# EnviroNode.net
KiCad netlist of a schematic drawn in Altium Designer
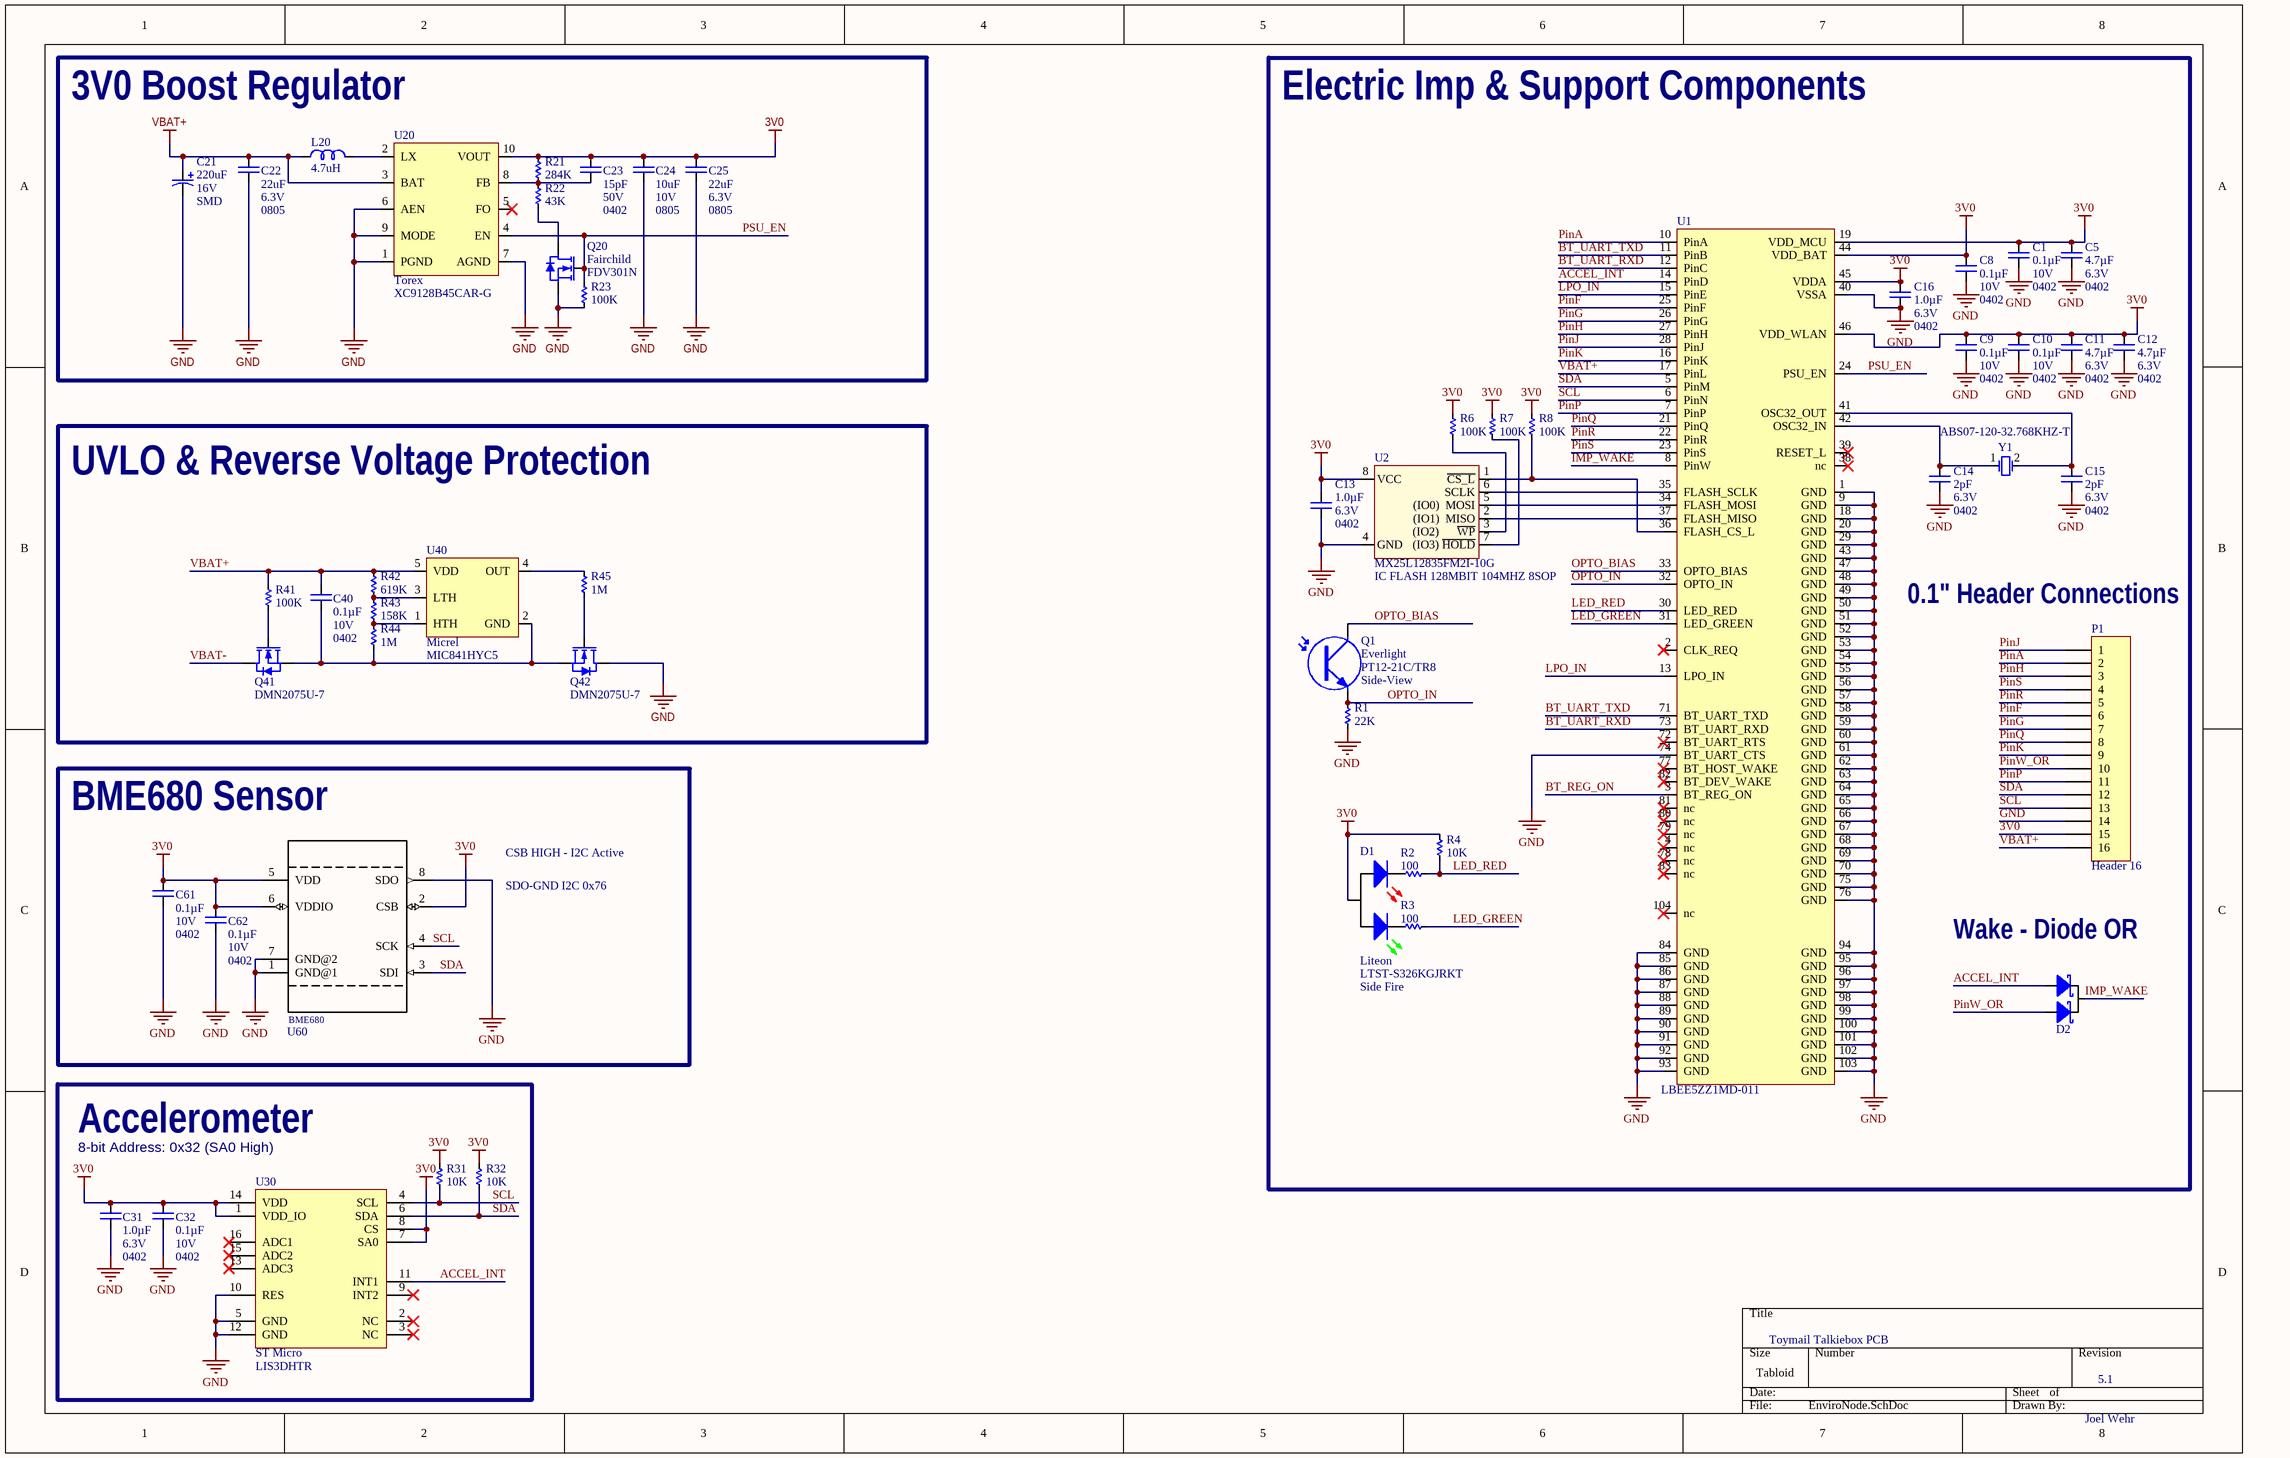
[diagram p0: EnviroNode.SchDoc]

(export (version "E")
  (design (tool "Eeschema 10.0.6"))
  (components
    (comp (ref "C1")
      (value "0.1µF")
      (footprint "Verified Components:CAPC1005X07N")
      (description "CAP CER 0.1UF 10V X5R 0402")
      (fields
        (field (name "TOLERANCE") "10%")
        (field (name "MANUFACTURER") "Taiyo Yuden")
        (field (name "VOLTAGE") "10V")
        (field (name "PACKAGE") "0402")
      )
      (libsource (lib "Verified Components") (part "CAP CER 0.1UF 10V X5R 0402"))
    )
    (comp (ref "C5")
      (value "4.7µF")
      (footprint "Verified Components:CAPC1005X07N")
      (description "CAP CER 4.7UF 6.3V X5R 0402")
      (fields
        (field (name "TOLERANCE") "10%")
        (field (name "MANUFACTURER") "Samsung Electro-Mechanics")
        (field (name "VOLTAGE") "6.3V")
        (field (name "PACKAGE") "0402")
      )
      (libsource (lib "Verified Components") (part "CAP CER 4.7UF 6.3V X5R 0402"))
    )
    (comp (ref "C8")
      (value "0.1µF")
      (footprint "Verified Components:CAPC1005X07N")
      (description "CAP CER 0.1UF 10V X5R 0402")
      (fields
        (field (name "TOLERANCE") "10%")
        (field (name "MANUFACTURER") "Taiyo Yuden")
        (field (name "VOLTAGE") "10V")
        (field (name "PACKAGE") "0402")
      )
      (libsource (lib "Verified Components") (part "CAP CER 0.1UF 10V X5R 0402"))
    )
    (comp (ref "C9")
      (value "0.1µF")
      (footprint "Verified Components:CAPC1005X07N")
      (description "CAP CER 0.1UF 10V X5R 0402")
      (fields
        (field (name "TOLERANCE") "10%")
        (field (name "MANUFACTURER") "Taiyo Yuden")
        (field (name "VOLTAGE") "10V")
        (field (name "PACKAGE") "0402")
      )
      (libsource (lib "Verified Components") (part "CAP CER 0.1UF 10V X5R 0402"))
    )
    (comp (ref "C10")
      (value "0.1µF")
      (footprint "Verified Components:CAPC1005X07N")
      (description "CAP CER 0.1UF 10V X5R 0402")
      (fields
        (field (name "TOLERANCE") "10%")
        (field (name "MANUFACTURER") "Taiyo Yuden")
        (field (name "VOLTAGE") "10V")
        (field (name "PACKAGE") "0402")
      )
      (libsource (lib "Verified Components") (part "CAP CER 0.1UF 10V X5R 0402"))
    )
    (comp (ref "C11")
      (value "4.7µF")
      (footprint "Verified Components:CAPC1005X07N")
      (description "CAP CER 4.7UF 6.3V X5R 0402")
      (fields
        (field (name "TOLERANCE") "10%")
        (field (name "MANUFACTURER") "Samsung Electro-Mechanics")
        (field (name "VOLTAGE") "6.3V")
        (field (name "PACKAGE") "0402")
      )
      (libsource (lib "Verified Components") (part "CAP CER 4.7UF 6.3V X5R 0402"))
    )
    (comp (ref "C12")
      (value "4.7µF")
      (footprint "Verified Components:CAPC1005X07N")
      (description "CAP CER 4.7UF 6.3V X5R 0402")
      (fields
        (field (name "TOLERANCE") "10%")
        (field (name "MANUFACTURER") "Samsung Electro-Mechanics")
        (field (name "VOLTAGE") "6.3V")
        (field (name "PACKAGE") "0402")
      )
      (libsource (lib "Verified Components") (part "CAP CER 4.7UF 6.3V X5R 0402"))
    )
    (comp (ref "C13")
      (value "1.0µF")
      (footprint "Verified Components:CAPC1005X07N")
      (description "CAP CER 1.0UF 6.3V X7R 0402")
      (fields
        (field (name "TOLERANCE") "10%")
        (field (name "VOLTAGE") "6.3V")
        (field (name "PACKAGE") "0402")
      )
      (libsource (lib "Verified Components") (part "CAP CER 1.0UF 6.3V X7R 0402"))
    )
    (comp (ref "C14")
      (value "2pF")
      (footprint "Verified Components:CAPC1005X07N")
      (description "CAP CER 2pF 6.3V X7R 0402")
      (fields
        (field (name "TOLERANCE") "10%")
        (field (name "VOLTAGE") "6.3V")
        (field (name "PACKAGE") "0402")
      )
      (libsource (lib "Verified Components") (part "CAP CER 2pF 6.3V X7R 0402"))
    )
    (comp (ref "C15")
      (value "2pF")
      (footprint "Verified Components:CAPC1005X07N")
      (description "CAP CER 2pF 6.3V X7R 0402")
      (fields
        (field (name "TOLERANCE") "10%")
        (field (name "VOLTAGE") "6.3V")
        (field (name "PACKAGE") "0402")
      )
      (libsource (lib "Verified Components") (part "CAP CER 2pF 6.3V X7R 0402"))
    )
    (comp (ref "C16")
      (value "1.0µF")
      (footprint "Verified Components:CAPC1005X07N")
      (description "CAP CER 1.0UF 6.3V X7R 0402")
      (fields
        (field (name "TOLERANCE") "10%")
        (field (name "VOLTAGE") "6.3V")
        (field (name "PACKAGE") "0402")
      )
      (libsource (lib "Verified Components") (part "CAP CER 1.0UF 6.3V X7R 0402"))
    )
    (comp (ref "C21")
      (value "220uF")
      (footprint "Verified Components:UWT1C221MCL1GS")
      (description "CAP,ALUM POLYMER,220uF,20%,16V,SMD")
      (fields
        (field (name "TOLERANCE") "20%")
        (field (name "PART NUMBER") "CAPP00124")
        (field (name "VOLTAGE") "16V")
        (field (name "PACKAGE") "SMD")
      )
      (libsource (lib "Verified Components") (part "CAP,ALUM POLYMER,220uF,20%,16V,SMD"))
    )
    (comp (ref "C22")
      (value "22uF")
      (footprint "Verified Components:CAPC2012X14N")
      (description "CAP CER 22UF 6.3V X5R 0805")
      (fields
        (field (name "TOLERANCE") "20%")
        (field (name "PART NUMBER") "CAPC00039")
        (field (name "VOLTAGE") "6.3V")
        (field (name "PACKAGE") "0805")
      )
      (libsource (lib "Verified Components") (part "CAP CER 22UF 6.3V X5R 0805"))
    )
    (comp (ref "C23")
      (value "15pF")
      (footprint "Verified Components:CAPC1005X07N")
      (description "CAP CER 15PF 50V C0G/NP0 0402")
      (fields
        (field (name "TOLERANCE") "5%")
        (field (name "MANUFACTURER") "Murata Electronics North America")
        (field (name "VOLTAGE") "50V")
        (field (name "PACKAGE") "0402")
      )
      (libsource (lib "Verified Components") (part "CAP CER 13PF 50V C0G/NP0 0402"))
    )
    (comp (ref "C24")
      (value "10uF")
      (footprint "Verified Components:CAPC2012X14N")
      (description "CAP CER 10UF 10V X5R 0805")
      (fields
        (field (name "TOLERANCE") "20%")
        (field (name "PART NUMBER") "CAPC00039")
        (field (name "VOLTAGE") "10V")
        (field (name "PACKAGE") "0805")
      )
      (libsource (lib "Verified Components") (part "CAP CER 10UF 10V X5R 0805"))
    )
    (comp (ref "C25")
      (value "22uF")
      (footprint "Verified Components:CAPC2012X14N")
      (description "CAP CER 22UF 6.3V X5R 0805")
      (fields
        (field (name "TOLERANCE") "20%")
        (field (name "PART NUMBER") "CAPC00039")
        (field (name "VOLTAGE") "6.3V")
        (field (name "PACKAGE") "0805")
      )
      (libsource (lib "Verified Components") (part "CAP CER 22UF 6.3V X5R 0805"))
    )
    (comp (ref "C31")
      (value "1.0µF")
      (footprint "Verified Components:CAPC1005X07N")
      (description "CAP CER 1.0UF 6.3V X7R 0402")
      (fields
        (field (name "TOLERANCE") "10%")
        (field (name "VOLTAGE") "6.3V")
        (field (name "PACKAGE") "0402")
      )
      (libsource (lib "Verified Components") (part "CAP CER 1.0UF 6.3V X7R 0402"))
    )
    (comp (ref "C32")
      (value "0.1µF")
      (footprint "Verified Components:CAPC1005X07N")
      (description "CAP CER 0.1UF 10V X5R 0402")
      (fields
        (field (name "TOLERANCE") "10%")
        (field (name "MANUFACTURER") "Taiyo Yuden")
        (field (name "VOLTAGE") "10V")
        (field (name "PACKAGE") "0402")
      )
      (libsource (lib "Verified Components") (part "CAP CER 0.1UF 10V X5R 0402"))
    )
    (comp (ref "C40")
      (value "0.1µF")
      (footprint "Verified Components:CAPC1005X07N")
      (description "CAP CER 0.1UF 10V X5R 0402")
      (fields
        (field (name "TOLERANCE") "10%")
        (field (name "MANUFACTURER") "Taiyo Yuden")
        (field (name "VOLTAGE") "10V")
        (field (name "PACKAGE") "0402")
      )
      (libsource (lib "Verified Components") (part "CAP CER 0.1UF 10V X5R 0402"))
    )
    (comp (ref "C61")
      (value "0.1µF")
      (footprint "Verified Components:CAPC1005X07N")
      (description "CAP CER 0.1UF 10V X5R 0402")
      (fields
        (field (name "TOLERANCE") "10%")
        (field (name "MANUFACTURER") "Taiyo Yuden")
        (field (name "VOLTAGE") "10V")
        (field (name "PACKAGE") "0402")
      )
      (libsource (lib "Verified Components") (part "CAP CER 0.1UF 10V X5R 0402"))
    )
    (comp (ref "C62")
      (value "0.1µF")
      (footprint "Verified Components:CAPC1005X07N")
      (description "CAP CER 0.1UF 10V X5R 0402")
      (fields
        (field (name "TOLERANCE") "10%")
        (field (name "MANUFACTURER") "Taiyo Yuden")
        (field (name "VOLTAGE") "10V")
        (field (name "PACKAGE") "0402")
      )
      (libsource (lib "Verified Components") (part "CAP CER 0.1UF 10V X5R 0402"))
    )
    (comp (ref "D1")
      (value "LED Red and Green")
      (footprint "Verified Components:LTST-S326KGJRKT")
      (description "LED, Dual, Side-view, Red-Green,2V, Common Anode, SMT")
      (fields
        (field (name "PART NUMBER") "LED00016")
        (field (name "MANUFACTURER") "Liteon")
        (field (name "MANUFACTURER PART NUMBER") "LTST-S326KGJRKT")
        (field (name "ORIENTATION") "Side Fire")
      )
      (libsource (lib "Verified Components") (part "LED_REDGREEN_CA"))
    )
    (comp (ref "D2")
      (value "Dual Schottky Diode")
      (footprint "Verified Components:SOT95P300X130-3N")
      (description "DIODE, Schottky, 200mA, 30V, Dual, Common Cathode, SOT23")
      (fields (field (name "PART NUMBER") "SCHOTTKY00009") (field (name "MANUFACTURER") "Fairchild"))
      (libsource (lib "Verified Components") (part "BAT54C"))
    )
    (comp (ref "L20")
      (value "4.7uH")
      (footprint "Verified Components:INDP6060X28N")
      (description "FIXED IND 4.7UH 3A 40.3 MOHM SMD")
      (fields (field (name "PART NUMBER") "IND00007") (field (name "MANUFACTURER") "Taiyo Yuden"))
      (libsource (lib "Verified Components") (part "NR6028T4R7M"))
    )
    (comp (ref "P1")
      (value "Header 16")
      (footprint "HDR1X16")
      (description "Header, 16-Pin")
      (fields (field (name "PUBLISHER") "Altium Limited"))
      (libsource (lib "Miscellaneous Connectors") (part "Header 16"))
    )
    (comp (ref "Q1")
      (value "PHOTOTRANSISTOR")
      (footprint "Verified Components:PT12-21C")
      (description "Phototrans, Clear, Side-view, 940nm, 0.4V, 1.14mA, SMT")
      (fields
        (field (name "PART NUMBER") "PHOTO00004")
        (field (name "MANUFACTURER") "Everlight")
        (field (name "MANUFACTURER PART NUMBER") "PT12-21C/TR8")
        (field (name "ORIENTATION") "Side-View")
      )
      (libsource (lib "Verified Components") (part "PHOTOTRANSISTOR"))
    )
    (comp (ref "Q20")
      (value "N-Channel MOSFET")
      (footprint "SOT95P300X130-3N")
      (description "NFET")
      (fields
        (field (name "PART NUMBER") "NFET00004")
        (field (name "MANUFACTURER") "Fairchild")
        (field (name "MANUFACTURER PART NUMBER") "FDV301N")
      )
      (libsource (lib "Verified Components") (part "DMN2075U-7"))
    )
    (comp (ref "Q41")
      (value "N-Channel MOSFET")
      (footprint "Verified Components:SOT95P300X130-3N")
      (description "NFET, 20V, 4.2A, SOT23")
      (fields
        (field (name "PART NUMBER") "NFET00004")
        (field (name "MANUFACTURER") "Diodes Incorporated")
        (field (name "MANUFACTURER PART NUMBER") "DMN2075U-7")
      )
      (libsource (lib "Verified Components") (part "DMN2075U-7"))
    )
    (comp (ref "Q42")
      (value "N-Channel MOSFET")
      (footprint "SOT95P300X130-3N")
      (description "NFET, 20V, 4.2A, SOT23")
      (fields
        (field (name "PART NUMBER") "NFET00004")
        (field (name "MANUFACTURER") "Diodes Incorporated")
        (field (name "MANUFACTURER PART NUMBER") "DMN2075U-7")
      )
      (libsource (lib "Verified Components") (part "DMN2075U-7"))
    )
    (comp (ref "R1")
      (value "22K")
      (footprint "Verified Components:RESC1005X04N")
      (description "RES SMD 22K OHM 1% 1/16W 0402")
      (fields (field (name "POWER") "0.063W") (field (name "MANUFACTURER") "Samsung"))
      (libsource (lib "Verified Components") (part "RES SMD 22K OHM 1% 1/16W 0402"))
    )
    (comp (ref "R2")
      (value "100")
      (footprint "Verified Components:RESC1005X04N")
      (description "RES SMD 100 OHM 5% 1/16W 0402")
      (fields (field (name "POWER") "0.063W") (field (name "TOLERANCE") "5%"))
      (libsource (lib "Verified Components") (part "RES SMD 100 OHM 5% 1/16W 0402"))
    )
    (comp (ref "R3")
      (value "100")
      (footprint "Verified Components:RESC1005X04N")
      (description "RES SMD 100 OHM 5% 1/16W 0402")
      (fields (field (name "POWER") "0.063W") (field (name "TOLERANCE") "5%"))
      (libsource (lib "Verified Components") (part "RES SMD 100 OHM 5% 1/16W 0402"))
    )
    (comp (ref "R4")
      (value "10K")
      (footprint "Verified Components:RESC1005X04N")
      (description "RES SMD 10K OHM 1% 1/16W 0402")
      (fields (field (name "POWER") "0.063W") (field (name "TOLERANCE") "1%"))
      (libsource (lib "Verified Components") (part "RES SMD 10K OHM 1% 1/16W 0402"))
    )
    (comp (ref "R6")
      (value "100K")
      (footprint "Verified Components:RESC1005X04N")
      (description "RES SMD 100K OHM 5% 1/16W 0402")
      (fields (field (name "PART NUMBER") "RES00001") (field (name "POWER") "0.063W"))
      (libsource (lib "Verified Components") (part "RES SMD 100K OHM 5% 1/16W 0402"))
    )
    (comp (ref "R7")
      (value "100K")
      (footprint "Verified Components:RESC1005X04N")
      (description "RES SMD 100K OHM 5% 1/16W 0402")
      (fields (field (name "PART NUMBER") "RES00001") (field (name "POWER") "0.063W"))
      (libsource (lib "Verified Components") (part "RES SMD 100K OHM 5% 1/16W 0402"))
    )
    (comp (ref "R8")
      (value "100K")
      (footprint "Verified Components:RESC1005X04N")
      (description "RES SMD 100K OHM 5% 1/16W 0402")
      (fields (field (name "PART NUMBER") "RES00001") (field (name "POWER") "0.063W"))
      (libsource (lib "Verified Components") (part "RES SMD 100K OHM 5% 1/16W 0402"))
    )
    (comp (ref "R21")
      (value "284K")
      (footprint "Verified Components:RESC1005X04N")
      (description "RES SMD 220K OHM 1% 1/16W 0402")
      (fields (field (name "POWER") "0.063W") (field (name "MANUFACTURER") "Samsung"))
      (libsource (lib "Verified Components") (part "RES SMD 22K OHM 1% 1/16W 0402"))
    )
    (comp (ref "R22")
      (value "43K")
      (footprint "Verified Components:RESC1005X04N")
      (description "RES SMD 43K OHM 1% 1/16W 0402")
      (fields (field (name "POWER") "0.063W") (field (name "MANUFACTURER") "Samsung"))
      (libsource (lib "Verified Components") (part "RES SMD 22K OHM 1% 1/16W 0402"))
    )
    (comp (ref "R23")
      (value "100K")
      (footprint "Verified Components:RESC1005X04N")
      (description "RES SMD 100K OHM 5% 1/16W 0402")
      (fields (field (name "PART NUMBER") "RES00001") (field (name "POWER") "0.063W"))
      (libsource (lib "Verified Components") (part "RES SMD 100K OHM 5% 1/16W 0402"))
    )
    (comp (ref "R31")
      (value "10K")
      (footprint "Verified Components:RESC1005X04N")
      (description "RES SMD 10K OHM 1% 1/16W 0402")
      (fields (field (name "POWER") "0.063W") (field (name "TOLERANCE") "1%"))
      (libsource (lib "Verified Components") (part "RES SMD 10K OHM 1% 1/16W 0402"))
    )
    (comp (ref "R32")
      (value "10K")
      (footprint "Verified Components:RESC1005X04N")
      (description "RES SMD 10K OHM 1% 1/16W 0402")
      (fields (field (name "POWER") "0.063W") (field (name "TOLERANCE") "1%"))
      (libsource (lib "Verified Components") (part "RES SMD 10K OHM 1% 1/16W 0402"))
    )
    (comp (ref "R41")
      (value "100K")
      (footprint "Verified Components:RESC1005X04N")
      (description "RES SMD 100K OHM 5% 1/16W 0402")
      (fields (field (name "PART NUMBER") "RES00001") (field (name "POWER") "0.063W"))
      (libsource (lib "Verified Components") (part "RES SMD 100K OHM 5% 1/16W 0402"))
    )
    (comp (ref "R42")
      (value "619K")
      (footprint "Verified Components:RESC1005X04N")
      (description "RES SMD 1M OHM 1% 1/16W 0402")
      (fields (field (name "POWER") "0.063W") (field (name "MANUFACTURER") "Samsung"))
      (libsource (lib "Verified Components") (part "RES SMD 1M OHM 1% 1/16W 0402"))
    )
    (comp (ref "R43")
      (value "158K")
      (footprint "Verified Components:RESC1005X04N")
      (description "RES SMD 1M OHM 1% 1/16W 0402")
      (fields (field (name "POWER") "0.063W") (field (name "MANUFACTURER") "Samsung"))
      (libsource (lib "Verified Components") (part "RES SMD 1M OHM 1% 1/16W 0402"))
    )
    (comp (ref "R44")
      (value "1M")
      (footprint "Verified Components:RESC1005X04N")
      (description "RES SMD 1M OHM 1% 1/16W 0402")
      (fields (field (name "POWER") "0.063W") (field (name "MANUFACTURER") "Samsung"))
      (libsource (lib "Verified Components") (part "RES SMD 1M OHM 1% 1/16W 0402"))
    )
    (comp (ref "R45")
      (value "1M")
      (footprint "Verified Components:RESC1005X04N")
      (description "RES SMD 1M OHM 1% 1/16W 0402")
      (fields (field (name "POWER") "0.063W") (field (name "MANUFACTURER") "Samsung"))
      (libsource (lib "Verified Components") (part "RES SMD 1M OHM 1% 1/16W 0402"))
    )
    (comp (ref "U1")
      (value "Murata Imp004m Module")
      (footprint "Verified Components:LBEE5ZZ1MD")
      (fields
        (field (name "MANUFACTURER") "Murata Electronics North America")
        (field (name "MANUFACTURER PART NUMBER") "LBEE5ZZ1MD-011")
      )
      (libsource (lib "Integrated_Library") (part "LBEE5ZZ1MD"))
    )
    (comp (ref "U2")
      (value "IC FLASH 128MBIT 104MHZ 8SOP")
      (footprint "Verified Components:SOP127P790X216-8N")
      (fields
        (field (name "MANUFACTURER") "Macronix")
        (field (name "MANUFACTURER PART NUMBER") "MX25L12835FM2I-10G")
      )
      (libsource (lib "Verified Components") (part "IC FLASH 128MBIT 104MHZ 8SOP"))
    )
    (comp (ref "U20")
      (value "XC9128")
      (footprint "MSOP50P490X116-10N")
      (description "IC, DC/DC boost,Adjustable, 6 VIN, 500mA, MSOP10")
      (fields
        (field (name "PART NUMBER") "IC00026")
        (field (name "MANUFACTURER") "Torex")
        (field (name "MANUFACTURER PART NUMBER") "XC9128B45CAR-G")
      )
      (libsource (lib "Verified Components") (part "XC9128"))
    )
    (comp (ref "U30")
      (value "LIS3DHTR")
      (footprint "Verified Components:LGA50P300X300X100-16N-ST")
      (description "IC, Accelerometer, 3-Axis, Low Power, 16-bit, LGA16")
      (fields
        (field (name "PART NUMBER") "IC00038")
        (field (name "MANUFACTURER") "ST Micro")
        (field (name "MANUFACTURER PART NUMBER") "LIS3DHTR")
      )
      (libsource (lib "Verified Components") (part "LIS3DHTR"))
    )
    (comp (ref "U40")
      (value "MIC841")
      (footprint "Verified Components:SOT65P200X125-5N")
      (description "IC, Comparator with Reference and Programmable Hysteresis, SOT-353")
      (fields
        (field (name "PART NUMBER") "IC00032")
        (field (name "MANUFACTURER") "Micrel")
        (field (name "MANUFACTURER PART NUMBER") "MIC841HYC5")
      )
      (libsource (lib "Verified Components") (part "MIC841"))
    )
    (comp (ref "U60")
      (value "BME680")
      (footprint "Verified Components:BME680")
      (description "Integrated Environmental Unit")
      (fields (field (name "MF") "Bosch"))
      (libsource (lib "Verified Components") (part "BME680"))
    )
    (comp (ref "Y1")
      (value "XTAL_COMPACT")
      (footprint "Verified Components:XTAL_32X15X09-2N")
      (description "XTAL, 32.768kHz, 20ppm, 6pF, 60K Ohm, 3215")
      (fields
        (field (name "MANUFACTURER") "Abracon")
        (field (name "PART NUMBER") "XTAL00004")
        (field (name "MANUFACTURER PART NUMBER") "ABS07-120-32.768KHZ-T")
      )
      (libsource (lib "Verified Components") (part "XTAL_COMPACT"))
    )
  )
  (nets
    (net (code "1") (name "/ACCEL_INT") (class "Default")
      (node (ref "D2") (pin "1") (pinfunction "1_1") (pintype "passive"))
      (node (ref "U1") (pin "14") (pinfunction "PinD_14") (pintype "passive"))
      (node (ref "U30") (pin "11") (pinfunction "INT1_11") (pintype "passive"))
    )
    (net (code "2") (name "/BT_REG_ON") (class "Default")
      (node (ref "U1") (pin "3") (pinfunction "BT_REG_ON_3") (pintype "passive"))
    )
    (net (code "3") (name "/BT_UART_RXD") (class "Default")
      (node (ref "U1") (pin "12") (pinfunction "PinC_12") (pintype "passive"))
      (node (ref "U1") (pin "73") (pinfunction "BT_UART_RXD_73") (pintype "passive"))
    )
    (net (code "4") (name "/BT_UART_TXD") (class "Default")
      (node (ref "U1") (pin "11") (pinfunction "PinB_11") (pintype "passive"))
      (node (ref "U1") (pin "71") (pinfunction "BT_UART_TXD_71") (pintype "passive"))
    )
    (net (code "5") (name "/IMP_WAKE") (class "Default")
      (node (ref "D2") (pin "3") (pinfunction "3_3") (pintype "passive"))
      (node (ref "U1") (pin "8") (pinfunction "PinW_8") (pintype "passive"))
    )
    (net (code "6") (name "/LED_GREEN") (class "Default")
      (node (ref "R3") (pin "2") (pinfunction "2_2") (pintype "passive"))
      (node (ref "U1") (pin "31") (pinfunction "LED_GREEN_31") (pintype "passive"))
    )
    (net (code "7") (name "/LED_RED") (class "Default")
      (node (ref "R2") (pin "2") (pinfunction "2_2") (pintype "passive"))
      (node (ref "R4") (pin "2") (pinfunction "2_2") (pintype "passive"))
      (node (ref "U1") (pin "30") (pinfunction "LED_RED_30") (pintype "passive"))
    )
    (net (code "8") (name "/LPO_IN") (class "Default")
      (node (ref "U1") (pin "13") (pinfunction "LPO_IN_13") (pintype "passive"))
      (node (ref "U1") (pin "15") (pinfunction "PinE_15") (pintype "passive"))
    )
    (net (code "9") (name "/OPTO_BIAS") (class "Default")
      (node (ref "Q1") (pin "C") (pinfunction "C_C") (pintype "passive"))
      (node (ref "U1") (pin "33") (pinfunction "OPTO_BIAS_33") (pintype "passive"))
    )
    (net (code "10") (name "/OPTO_IN") (class "Default")
      (node (ref "Q1") (pin "E") (pinfunction "E_E") (pintype "passive"))
      (node (ref "R1") (pin "1") (pinfunction "1_1") (pintype "passive"))
      (node (ref "U1") (pin "32") (pinfunction "OPTO_IN_32") (pintype "passive"))
    )
    (net (code "11") (name "/PSU_EN") (class "Default")
      (node (ref "Q20") (pin "1") (pinfunction "G_1") (pintype "passive"))
      (node (ref "R23") (pin "1") (pinfunction "1_1") (pintype "passive"))
      (node (ref "U1") (pin "24") (pinfunction "PSU_EN_24") (pintype "passive"))
      (node (ref "U20") (pin "4") (pinfunction "EN_4") (pintype "passive"))
    )
    (net (code "12") (name "/PinA") (class "Default")
      (node (ref "P1") (pin "2") (pinfunction "2_2") (pintype "passive"))
      (node (ref "U1") (pin "10") (pinfunction "PinA_10") (pintype "passive"))
    )
    (net (code "13") (name "/PinF") (class "Default")
      (node (ref "P1") (pin "6") (pinfunction "6_6") (pintype "passive"))
      (node (ref "U1") (pin "25") (pinfunction "PinF_25") (pintype "passive"))
    )
    (net (code "14") (name "/PinG") (class "Default")
      (node (ref "P1") (pin "7") (pinfunction "7_7") (pintype "passive"))
      (node (ref "U1") (pin "26") (pinfunction "PinG_26") (pintype "passive"))
    )
    (net (code "15") (name "/PinH") (class "Default")
      (node (ref "P1") (pin "3") (pinfunction "3_3") (pintype "passive"))
      (node (ref "U1") (pin "27") (pinfunction "PinH_27") (pintype "passive"))
    )
    (net (code "16") (name "/PinJ") (class "Default")
      (node (ref "P1") (pin "1") (pinfunction "1_1") (pintype "passive"))
      (node (ref "U1") (pin "28") (pinfunction "PinJ_28") (pintype "passive"))
    )
    (net (code "17") (name "/PinK") (class "Default")
      (node (ref "P1") (pin "9") (pinfunction "9_9") (pintype "passive"))
      (node (ref "U1") (pin "16") (pinfunction "PinK_16") (pintype "passive"))
    )
    (net (code "18") (name "/PinP") (class "Default")
      (node (ref "P1") (pin "11") (pinfunction "11_11") (pintype "passive"))
      (node (ref "U1") (pin "7") (pinfunction "PinP_7") (pintype "passive"))
    )
    (net (code "19") (name "/PinQ") (class "Default")
      (node (ref "P1") (pin "8") (pinfunction "8_8") (pintype "passive"))
      (node (ref "U1") (pin "21") (pinfunction "PinQ_21") (pintype "passive"))
    )
    (net (code "20") (name "/PinR") (class "Default")
      (node (ref "P1") (pin "5") (pinfunction "5_5") (pintype "passive"))
      (node (ref "U1") (pin "22") (pinfunction "PinR_22") (pintype "passive"))
    )
    (net (code "21") (name "/PinS") (class "Default")
      (node (ref "P1") (pin "4") (pinfunction "4_4") (pintype "passive"))
      (node (ref "U1") (pin "23") (pinfunction "PinS_23") (pintype "passive"))
    )
    (net (code "22") (name "/PinW_OR") (class "Default")
      (node (ref "D2") (pin "2") (pinfunction "2_2") (pintype "open_emitter"))
      (node (ref "P1") (pin "10") (pinfunction "10_10") (pintype "passive"))
    )
    (net (code "23") (name "/SCL") (class "Default")
      (node (ref "P1") (pin "13") (pinfunction "13_13") (pintype "passive"))
      (node (ref "R31") (pin "2") (pinfunction "2_2") (pintype "passive"))
      (node (ref "U1") (pin "6") (pinfunction "PinN_6") (pintype "passive"))
      (node (ref "U30") (pin "4") (pinfunction "SCL_4") (pintype "passive"))
      (node (ref "U60") (pin "4") (pinfunction "SCK_4") (pintype "input"))
    )
    (net (code "24") (name "/SDA") (class "Default")
      (node (ref "P1") (pin "12") (pinfunction "12_12") (pintype "passive"))
      (node (ref "R32") (pin "2") (pinfunction "2_2") (pintype "passive"))
      (node (ref "U1") (pin "5") (pinfunction "PinM_5") (pintype "passive"))
      (node (ref "U30") (pin "6") (pinfunction "SDA_6") (pintype "passive"))
      (node (ref "U60") (pin "3") (pinfunction "SDI_3") (pintype "input"))
    )
    (net (code "25") (name "/VBAT-") (class "Default")
      (node (ref "Q41") (pin "3") (pinfunction "D_3") (pintype "passive"))
    )
    (net (code "26") (name "3V0") (class "Default")
      (node (ref "C1") (pin "2") (pinfunction "2_2") (pintype "passive"))
      (node (ref "C10") (pin "2") (pinfunction "2_2") (pintype "passive"))
      (node (ref "C11") (pin "2") (pinfunction "2_2") (pintype "passive"))
      (node (ref "C12") (pin "2") (pinfunction "2_2") (pintype "passive"))
      (node (ref "C13") (pin "2") (pinfunction "2_2") (pintype "passive"))
      (node (ref "C16") (pin "2") (pinfunction "2_2") (pintype "passive"))
      (node (ref "C23") (pin "2") (pinfunction "2_2") (pintype "passive"))
      (node (ref "C24") (pin "2") (pinfunction "2_2") (pintype "passive"))
      (node (ref "C25") (pin "2") (pinfunction "2_2") (pintype "passive"))
      (node (ref "C31") (pin "2") (pinfunction "2_2") (pintype "passive"))
      (node (ref "C32") (pin "2") (pinfunction "2_2") (pintype "passive"))
      (node (ref "C5") (pin "2") (pinfunction "2_2") (pintype "passive"))
      (node (ref "C61") (pin "2") (pinfunction "2_2") (pintype "passive"))
      (node (ref "C62") (pin "2") (pinfunction "2_2") (pintype "passive"))
      (node (ref "C8") (pin "2") (pinfunction "2_2") (pintype "passive"))
      (node (ref "C9") (pin "2") (pinfunction "2_2") (pintype "passive"))
      (node (ref "D1") (pin "A") (pinfunction "A_A") (pintype "passive"))
      (node (ref "P1") (pin "15") (pinfunction "15_15") (pintype "passive"))
      (node (ref "R21") (pin "1") (pinfunction "1_1") (pintype "passive"))
      (node (ref "R31") (pin "1") (pinfunction "1_1") (pintype "passive"))
      (node (ref "R32") (pin "1") (pinfunction "1_1") (pintype "passive"))
      (node (ref "R4") (pin "1") (pinfunction "1_1") (pintype "passive"))
      (node (ref "R6") (pin "1") (pinfunction "1_1") (pintype "passive"))
      (node (ref "R7") (pin "1") (pinfunction "1_1") (pintype "passive"))
      (node (ref "R8") (pin "1") (pinfunction "1_1") (pintype "passive"))
      (node (ref "U1") (pin "19") (pinfunction "VDD_MCU_19") (pintype "passive"))
      (node (ref "U1") (pin "44") (pinfunction "VDD_BAT_44") (pintype "passive"))
      (node (ref "U1") (pin "45") (pinfunction "VDDA_45") (pintype "passive"))
      (node (ref "U1") (pin "46") (pinfunction "VDD_WLAN_46") (pintype "passive"))
      (node (ref "U2") (pin "8") (pinfunction "VCC_8") (pintype "power_in"))
      (node (ref "U20") (pin "10") (pinfunction "VOUT_10") (pintype "passive"))
      (node (ref "U30") (pin "1") (pinfunction "VDD_IO_1") (pintype "power_in"))
      (node (ref "U30") (pin "14") (pinfunction "VDD_14") (pintype "power_in"))
      (node (ref "U30") (pin "7") (pinfunction "SA0_7") (pintype "passive"))
      (node (ref "U30") (pin "8") (pinfunction "CS_8") (pintype "passive"))
      (node (ref "U60") (pin "2") (pinfunction "CSB_2") (pintype "bidirectional"))
      (node (ref "U60") (pin "5") (pinfunction "VDD_5") (pintype "power_in"))
      (node (ref "U60") (pin "6") (pinfunction "VDDIO_6") (pintype "bidirectional"))
    )
    (net (code "27") (name "GND") (class "Default")
      (node (ref "C1") (pin "1") (pinfunction "1_1") (pintype "passive"))
      (node (ref "C10") (pin "1") (pinfunction "1_1") (pintype "passive"))
      (node (ref "C11") (pin "1") (pinfunction "1_1") (pintype "passive"))
      (node (ref "C12") (pin "1") (pinfunction "1_1") (pintype "passive"))
      (node (ref "C13") (pin "1") (pinfunction "1_1") (pintype "passive"))
      (node (ref "C14") (pin "1") (pinfunction "1_1") (pintype "passive"))
      (node (ref "C15") (pin "1") (pinfunction "1_1") (pintype "passive"))
      (node (ref "C16") (pin "1") (pinfunction "1_1") (pintype "passive"))
      (node (ref "C21") (pin "2") (pinfunction "2_2") (pintype "passive"))
      (node (ref "C22") (pin "1") (pinfunction "1_1") (pintype "passive"))
      (node (ref "C24") (pin "1") (pinfunction "1_1") (pintype "passive"))
      (node (ref "C25") (pin "1") (pinfunction "1_1") (pintype "passive"))
      (node (ref "C31") (pin "1") (pinfunction "1_1") (pintype "passive"))
      (node (ref "C32") (pin "1") (pinfunction "1_1") (pintype "passive"))
      (node (ref "C5") (pin "1") (pinfunction "1_1") (pintype "passive"))
      (node (ref "C61") (pin "1") (pinfunction "1_1") (pintype "passive"))
      (node (ref "C62") (pin "1") (pinfunction "1_1") (pintype "passive"))
      (node (ref "C8") (pin "1") (pinfunction "1_1") (pintype "passive"))
      (node (ref "C9") (pin "1") (pinfunction "1_1") (pintype "passive"))
      (node (ref "P1") (pin "14") (pinfunction "14_14") (pintype "passive"))
      (node (ref "Q20") (pin "2") (pinfunction "S_2") (pintype "passive"))
      (node (ref "Q42") (pin "3") (pinfunction "D_3") (pintype "passive"))
      (node (ref "R1") (pin "2") (pinfunction "2_2") (pintype "passive"))
      (node (ref "R23") (pin "2") (pinfunction "2_2") (pintype "passive"))
      (node (ref "U1") (pin "1") (pinfunction "GND_1") (pintype "passive"))
      (node (ref "U1") (pin "100") (pinfunction "GND_100") (pintype "passive"))
      (node (ref "U1") (pin "101") (pinfunction "GND_101") (pintype "passive"))
      (node (ref "U1") (pin "102") (pinfunction "GND_102") (pintype "passive"))
      (node (ref "U1") (pin "103") (pinfunction "GND_103") (pintype "passive"))
      (node (ref "U1") (pin "18") (pinfunction "GND_18") (pintype "passive"))
      (node (ref "U1") (pin "20") (pinfunction "GND_20") (pintype "passive"))
      (node (ref "U1") (pin "29") (pinfunction "GND_29") (pintype "passive"))
      (node (ref "U1") (pin "40") (pinfunction "VSSA_40") (pintype "passive"))
      (node (ref "U1") (pin "43") (pinfunction "GND_43") (pintype "passive"))
      (node (ref "U1") (pin "47") (pinfunction "GND_47") (pintype "passive"))
      (node (ref "U1") (pin "48") (pinfunction "GND_48") (pintype "passive"))
      (node (ref "U1") (pin "49") (pinfunction "GND_49") (pintype "passive"))
      (node (ref "U1") (pin "50") (pinfunction "GND_50") (pintype "passive"))
      (node (ref "U1") (pin "51") (pinfunction "GND_51") (pintype "passive"))
      (node (ref "U1") (pin "52") (pinfunction "GND_52") (pintype "passive"))
      (node (ref "U1") (pin "53") (pinfunction "GND_53") (pintype "passive"))
      (node (ref "U1") (pin "54") (pinfunction "GND_54") (pintype "passive"))
      (node (ref "U1") (pin "55") (pinfunction "GND_55") (pintype "passive"))
      (node (ref "U1") (pin "56") (pinfunction "GND_56") (pintype "passive"))
      (node (ref "U1") (pin "57") (pinfunction "GND_57") (pintype "passive"))
      (node (ref "U1") (pin "58") (pinfunction "GND_58") (pintype "passive"))
      (node (ref "U1") (pin "59") (pinfunction "GND_59") (pintype "passive"))
      (node (ref "U1") (pin "60") (pinfunction "GND_60") (pintype "passive"))
      (node (ref "U1") (pin "61") (pinfunction "GND_61") (pintype "passive"))
      (node (ref "U1") (pin "62") (pinfunction "GND_62") (pintype "passive"))
      (node (ref "U1") (pin "63") (pinfunction "GND_63") (pintype "passive"))
      (node (ref "U1") (pin "64") (pinfunction "GND_64") (pintype "passive"))
      (node (ref "U1") (pin "65") (pinfunction "GND_65") (pintype "passive"))
      (node (ref "U1") (pin "66") (pinfunction "GND_66") (pintype "passive"))
      (node (ref "U1") (pin "67") (pinfunction "GND_67") (pintype "passive"))
      (node (ref "U1") (pin "68") (pinfunction "GND_68") (pintype "passive"))
      (node (ref "U1") (pin "69") (pinfunction "GND_69") (pintype "passive"))
      (node (ref "U1") (pin "70") (pinfunction "GND_70") (pintype "passive"))
      (node (ref "U1") (pin "74") (pinfunction "BT_UART_CTS_74") (pintype "passive"))
      (node (ref "U1") (pin "75") (pinfunction "GND_75") (pintype "passive"))
      (node (ref "U1") (pin "76") (pinfunction "GND_76") (pintype "passive"))
      (node (ref "U1") (pin "84") (pinfunction "GND_84") (pintype "passive"))
      (node (ref "U1") (pin "85") (pinfunction "GND_85") (pintype "passive"))
      (node (ref "U1") (pin "86") (pinfunction "GND_86") (pintype "passive"))
      (node (ref "U1") (pin "87") (pinfunction "GND_87") (pintype "passive"))
      (node (ref "U1") (pin "88") (pinfunction "GND_88") (pintype "passive"))
      (node (ref "U1") (pin "89") (pinfunction "GND_89") (pintype "passive"))
      (node (ref "U1") (pin "9") (pinfunction "GND_9") (pintype "passive"))
      (node (ref "U1") (pin "90") (pinfunction "GND_90") (pintype "passive"))
      (node (ref "U1") (pin "91") (pinfunction "GND_91") (pintype "passive"))
      (node (ref "U1") (pin "92") (pinfunction "GND_92") (pintype "passive"))
      (node (ref "U1") (pin "93") (pinfunction "GND_93") (pintype "passive"))
      (node (ref "U1") (pin "94") (pinfunction "GND_94") (pintype "passive"))
      (node (ref "U1") (pin "95") (pinfunction "GND_95") (pintype "passive"))
      (node (ref "U1") (pin "96") (pinfunction "GND_96") (pintype "passive"))
      (node (ref "U1") (pin "97") (pinfunction "GND_97") (pintype "passive"))
      (node (ref "U1") (pin "98") (pinfunction "GND_98") (pintype "passive"))
      (node (ref "U1") (pin "99") (pinfunction "GND_99") (pintype "passive"))
      (node (ref "U2") (pin "4") (pinfunction "GND_4") (pintype "power_in"))
      (node (ref "U20") (pin "1") (pinfunction "PGND_1") (pintype "passive"))
      (node (ref "U20") (pin "6") (pinfunction "AEN_6") (pintype "passive"))
      (node (ref "U20") (pin "7") (pinfunction "AGND_7") (pintype "passive"))
      (node (ref "U20") (pin "9") (pinfunction "MODE_9") (pintype "passive"))
      (node (ref "U30") (pin "10") (pinfunction "RES_10") (pintype "passive"))
      (node (ref "U30") (pin "12") (pinfunction "GND_12") (pintype "power_in"))
      (node (ref "U30") (pin "5") (pinfunction "GND_5") (pintype "power_in"))
      (node (ref "U60") (pin "1") (pinfunction "GND@1_1") (pintype "power_in"))
      (node (ref "U60") (pin "7") (pinfunction "GND@2_7") (pintype "power_in"))
      (node (ref "U60") (pin "8") (pinfunction "SDO_8") (pintype "output"))
    )
    (net (code "28") (name "Net-(D1-PadKG)") (class "Default")
      (node (ref "D1") (pin "KG") (pinfunction "KG_KG") (pintype "passive"))
      (node (ref "R3") (pin "1") (pinfunction "1_1") (pintype "passive"))
    )
    (net (code "29") (name "Net-(D1-PadKR)") (class "Default")
      (node (ref "D1") (pin "KR") (pinfunction "KR_KR") (pintype "passive"))
      (node (ref "R2") (pin "1") (pinfunction "1_1") (pintype "passive"))
    )
    (net (code "30") (name "Net-(Q20-D)") (class "Default")
      (node (ref "Q20") (pin "3") (pinfunction "D_3") (pintype "passive"))
      (node (ref "R22") (pin "2") (pinfunction "2_2") (pintype "passive"))
    )
    (net (code "31") (name "Net-(Q41-G)") (class "Default")
      (node (ref "Q41") (pin "1") (pinfunction "G_1") (pintype "passive"))
      (node (ref "R41") (pin "2") (pinfunction "2_2") (pintype "passive"))
    )
    (net (code "32") (name "Net-(Q41-S)") (class "Default")
      (node (ref "C40") (pin "1") (pinfunction "1_1") (pintype "passive"))
      (node (ref "Q41") (pin "2") (pinfunction "S_2") (pintype "passive"))
      (node (ref "Q42") (pin "2") (pinfunction "S_2") (pintype "passive"))
      (node (ref "R44") (pin "2") (pinfunction "2_2") (pintype "passive"))
      (node (ref "U40") (pin "2") (pinfunction "GND_2") (pintype "passive"))
    )
    (net (code "33") (name "Net-(Q42-G)") (class "Default")
      (node (ref "Q42") (pin "1") (pinfunction "G_1") (pintype "passive"))
      (node (ref "R45") (pin "2") (pinfunction "2_2") (pintype "passive"))
    )
    (net (code "34") (name "Net-(U1-FLASH_CS_L)") (class "Default")
      (node (ref "R8") (pin "2") (pinfunction "2_2") (pintype "passive"))
      (node (ref "U1") (pin "36") (pinfunction "FLASH_CS_L_36") (pintype "passive"))
      (node (ref "U2") (pin "1") (pinfunction "CS_L_1") (pintype "passive"))
    )
    (net (code "35") (name "Net-(U1-FLASH_MISO)") (class "Default")
      (node (ref "U1") (pin "37") (pinfunction "FLASH_MISO_37") (pintype "passive"))
      (node (ref "U2") (pin "2") (pinfunction "(IO1)__MISO_2") (pintype "passive"))
    )
    (net (code "36") (name "Net-(U1-FLASH_MOSI)") (class "Default")
      (node (ref "U1") (pin "34") (pinfunction "FLASH_MOSI_34") (pintype "passive"))
      (node (ref "U2") (pin "5") (pinfunction "(IO0)__MOSI_5") (pintype "passive"))
    )
    (net (code "37") (name "Net-(U1-FLASH_SCLK)") (class "Default")
      (node (ref "U1") (pin "35") (pinfunction "FLASH_SCLK_35") (pintype "passive"))
      (node (ref "U2") (pin "6") (pinfunction "SCLK_6") (pintype "passive"))
    )
    (net (code "38") (name "Net-(U1-OSC32_IN)") (class "Default")
      (node (ref "C14") (pin "2") (pinfunction "2_2") (pintype "passive"))
      (node (ref "U1") (pin "42") (pinfunction "OSC32_IN_42") (pintype "passive"))
      (node (ref "Y1") (pin "1") (pinfunction "OSC1_1") (pintype "passive"))
    )
    (net (code "39") (name "Net-(U1-OSC32_OUT)") (class "Default")
      (node (ref "C15") (pin "2") (pinfunction "2_2") (pintype "passive"))
      (node (ref "U1") (pin "41") (pinfunction "OSC32_OUT_41") (pintype "passive"))
      (node (ref "Y1") (pin "2") (pinfunction "OSC2_2") (pintype "passive"))
    )
    (net (code "40") (name "Net-(U2-(IO2)______~{WP})") (class "Default")
      (node (ref "R6") (pin "2") (pinfunction "2_2") (pintype "passive"))
      (node (ref "U2") (pin "3") (pinfunction "(IO2)______~{WP}_3") (pintype "passive"))
    )
    (net (code "41") (name "Net-(U2-(IO3)_~{HOLD})") (class "Default")
      (node (ref "R7") (pin "2") (pinfunction "2_2") (pintype "passive"))
      (node (ref "U2") (pin "7") (pinfunction "(IO3)_~{HOLD}_7") (pintype "passive"))
    )
    (net (code "42") (name "Net-(U20-FB)") (class "Default")
      (node (ref "C23") (pin "1") (pinfunction "1_1") (pintype "passive"))
      (node (ref "R21") (pin "2") (pinfunction "2_2") (pintype "passive"))
      (node (ref "R22") (pin "1") (pinfunction "1_1") (pintype "passive"))
      (node (ref "U20") (pin "8") (pinfunction "FB_8") (pintype "passive"))
    )
    (net (code "43") (name "Net-(U20-LX)") (class "Default")
      (node (ref "L20") (pin "2") (pinfunction "2_2") (pintype "passive"))
      (node (ref "U20") (pin "2") (pinfunction "LX_2") (pintype "passive"))
    )
    (net (code "44") (name "Net-(U40-HTH)") (class "Default")
      (node (ref "R43") (pin "2") (pinfunction "2_2") (pintype "passive"))
      (node (ref "R44") (pin "1") (pinfunction "1_1") (pintype "passive"))
      (node (ref "U40") (pin "1") (pinfunction "HTH_1") (pintype "passive"))
    )
    (net (code "45") (name "Net-(U40-LTH)") (class "Default")
      (node (ref "R42") (pin "2") (pinfunction "2_2") (pintype "passive"))
      (node (ref "R43") (pin "1") (pinfunction "1_1") (pintype "passive"))
      (node (ref "U40") (pin "3") (pinfunction "LTH_3") (pintype "passive"))
    )
    (net (code "46") (name "Net-(U40-OUT)") (class "Default")
      (node (ref "R45") (pin "1") (pinfunction "1_1") (pintype "passive"))
      (node (ref "U40") (pin "4") (pinfunction "OUT_4") (pintype "passive"))
    )
    (net (code "47") (name "VBAT+") (class "Default")
      (node (ref "C21") (pin "1") (pinfunction "1_1") (pintype "passive"))
      (node (ref "C22") (pin "2") (pinfunction "2_2") (pintype "passive"))
      (node (ref "C40") (pin "2") (pinfunction "2_2") (pintype "passive"))
      (node (ref "L20") (pin "1") (pinfunction "1_1") (pintype "passive"))
      (node (ref "P1") (pin "16") (pinfunction "16_16") (pintype "passive"))
      (node (ref "R41") (pin "1") (pinfunction "1_1") (pintype "passive"))
      (node (ref "R42") (pin "1") (pinfunction "1_1") (pintype "passive"))
      (node (ref "U1") (pin "17") (pinfunction "PinL_17") (pintype "passive"))
      (node (ref "U20") (pin "3") (pinfunction "BAT_3") (pintype "passive"))
      (node (ref "U40") (pin "5") (pinfunction "VDD_5") (pintype "passive"))
    )
    (net (code "48") (name "unconnected-(U1-BT_DEV_WAKE-Pad82)") (class "Default")
      (node (ref "U1") (pin "82") (pinfunction "BT_DEV_WAKE_82") (pintype "passive+no_connect"))
    )
    (net (code "49") (name "unconnected-(U1-BT_HOST_WAKE-Pad77)") (class "Default")
      (node (ref "U1") (pin "77") (pinfunction "BT_HOST_WAKE_77") (pintype "passive+no_connect"))
    )
    (net (code "50") (name "unconnected-(U1-BT_UART_RTS-Pad72)") (class "Default")
      (node (ref "U1") (pin "72") (pinfunction "BT_UART_RTS_72") (pintype "passive+no_connect"))
    )
    (net (code "51") (name "unconnected-(U1-CLK_REQ-Pad2)") (class "Default")
      (node (ref "U1") (pin "2") (pinfunction "CLK_REQ_2") (pintype "passive+no_connect"))
    )
    (net (code "52") (name "unconnected-(U1-RESET_L-Pad39)") (class "Default")
      (node (ref "U1") (pin "39") (pinfunction "RESET_L_39") (pintype "passive+no_connect"))
    )
    (net (code "53") (name "unconnected-(U1-nc-Pad4)") (class "Default")
      (node (ref "U1") (pin "4") (pinfunction "nc_4") (pintype "passive+no_connect"))
    )
    (net (code "54") (name "unconnected-(U1-nc-Pad38)") (class "Default")
      (node (ref "U1") (pin "38") (pinfunction "nc_38") (pintype "passive+no_connect"))
    )
    (net (code "55") (name "unconnected-(U1-nc-Pad78)") (class "Default")
      (node (ref "U1") (pin "78") (pinfunction "nc_78") (pintype "passive+no_connect"))
    )
    (net (code "56") (name "unconnected-(U1-nc-Pad79)") (class "Default")
      (node (ref "U1") (pin "79") (pinfunction "nc_79") (pintype "passive+no_connect"))
    )
    (net (code "57") (name "unconnected-(U1-nc-Pad80)") (class "Default")
      (node (ref "U1") (pin "80") (pinfunction "nc_80") (pintype "passive+no_connect"))
    )
    (net (code "58") (name "unconnected-(U1-nc-Pad81)") (class "Default")
      (node (ref "U1") (pin "81") (pinfunction "nc_81") (pintype "passive+no_connect"))
    )
    (net (code "59") (name "unconnected-(U1-nc-Pad83)") (class "Default")
      (node (ref "U1") (pin "83") (pinfunction "nc_83") (pintype "passive+no_connect"))
    )
    (net (code "60") (name "unconnected-(U1-nc-Pad104)") (class "Default")
      (node (ref "U1") (pin "104") (pinfunction "nc_104") (pintype "passive+no_connect"))
    )
    (net (code "61") (name "unconnected-(U20-FO-Pad5)") (class "Default")
      (node (ref "U20") (pin "5") (pinfunction "FO_5") (pintype "passive+no_connect"))
    )
    (net (code "62") (name "unconnected-(U30-ADC1-Pad16)") (class "Default")
      (node (ref "U30") (pin "16") (pinfunction "ADC1_16") (pintype "power_in+no_connect"))
    )
    (net (code "63") (name "unconnected-(U30-ADC2-Pad15)") (class "Default")
      (node (ref "U30") (pin "15") (pinfunction "ADC2_15") (pintype "passive+no_connect"))
    )
    (net (code "64") (name "unconnected-(U30-ADC3-Pad13)") (class "Default")
      (node (ref "U30") (pin "13") (pinfunction "ADC3_13") (pintype "power_in+no_connect"))
    )
    (net (code "65") (name "unconnected-(U30-INT2-Pad9)") (class "Default")
      (node (ref "U30") (pin "9") (pinfunction "INT2_9") (pintype "passive+no_connect"))
    )
    (net (code "66") (name "unconnected-(U30-NC-Pad2)") (class "Default")
      (node (ref "U30") (pin "2") (pinfunction "NC_2") (pintype "passive+no_connect"))
    )
    (net (code "67") (name "unconnected-(U30-NC-Pad3)") (class "Default")
      (node (ref "U30") (pin "3") (pinfunction "NC_3") (pintype "passive+no_connect"))
    )
  )
)
